# Atmega8_VAW_screen_easyEDA_source.net
KiCad netlist of a schematic drawn in EasyEDA
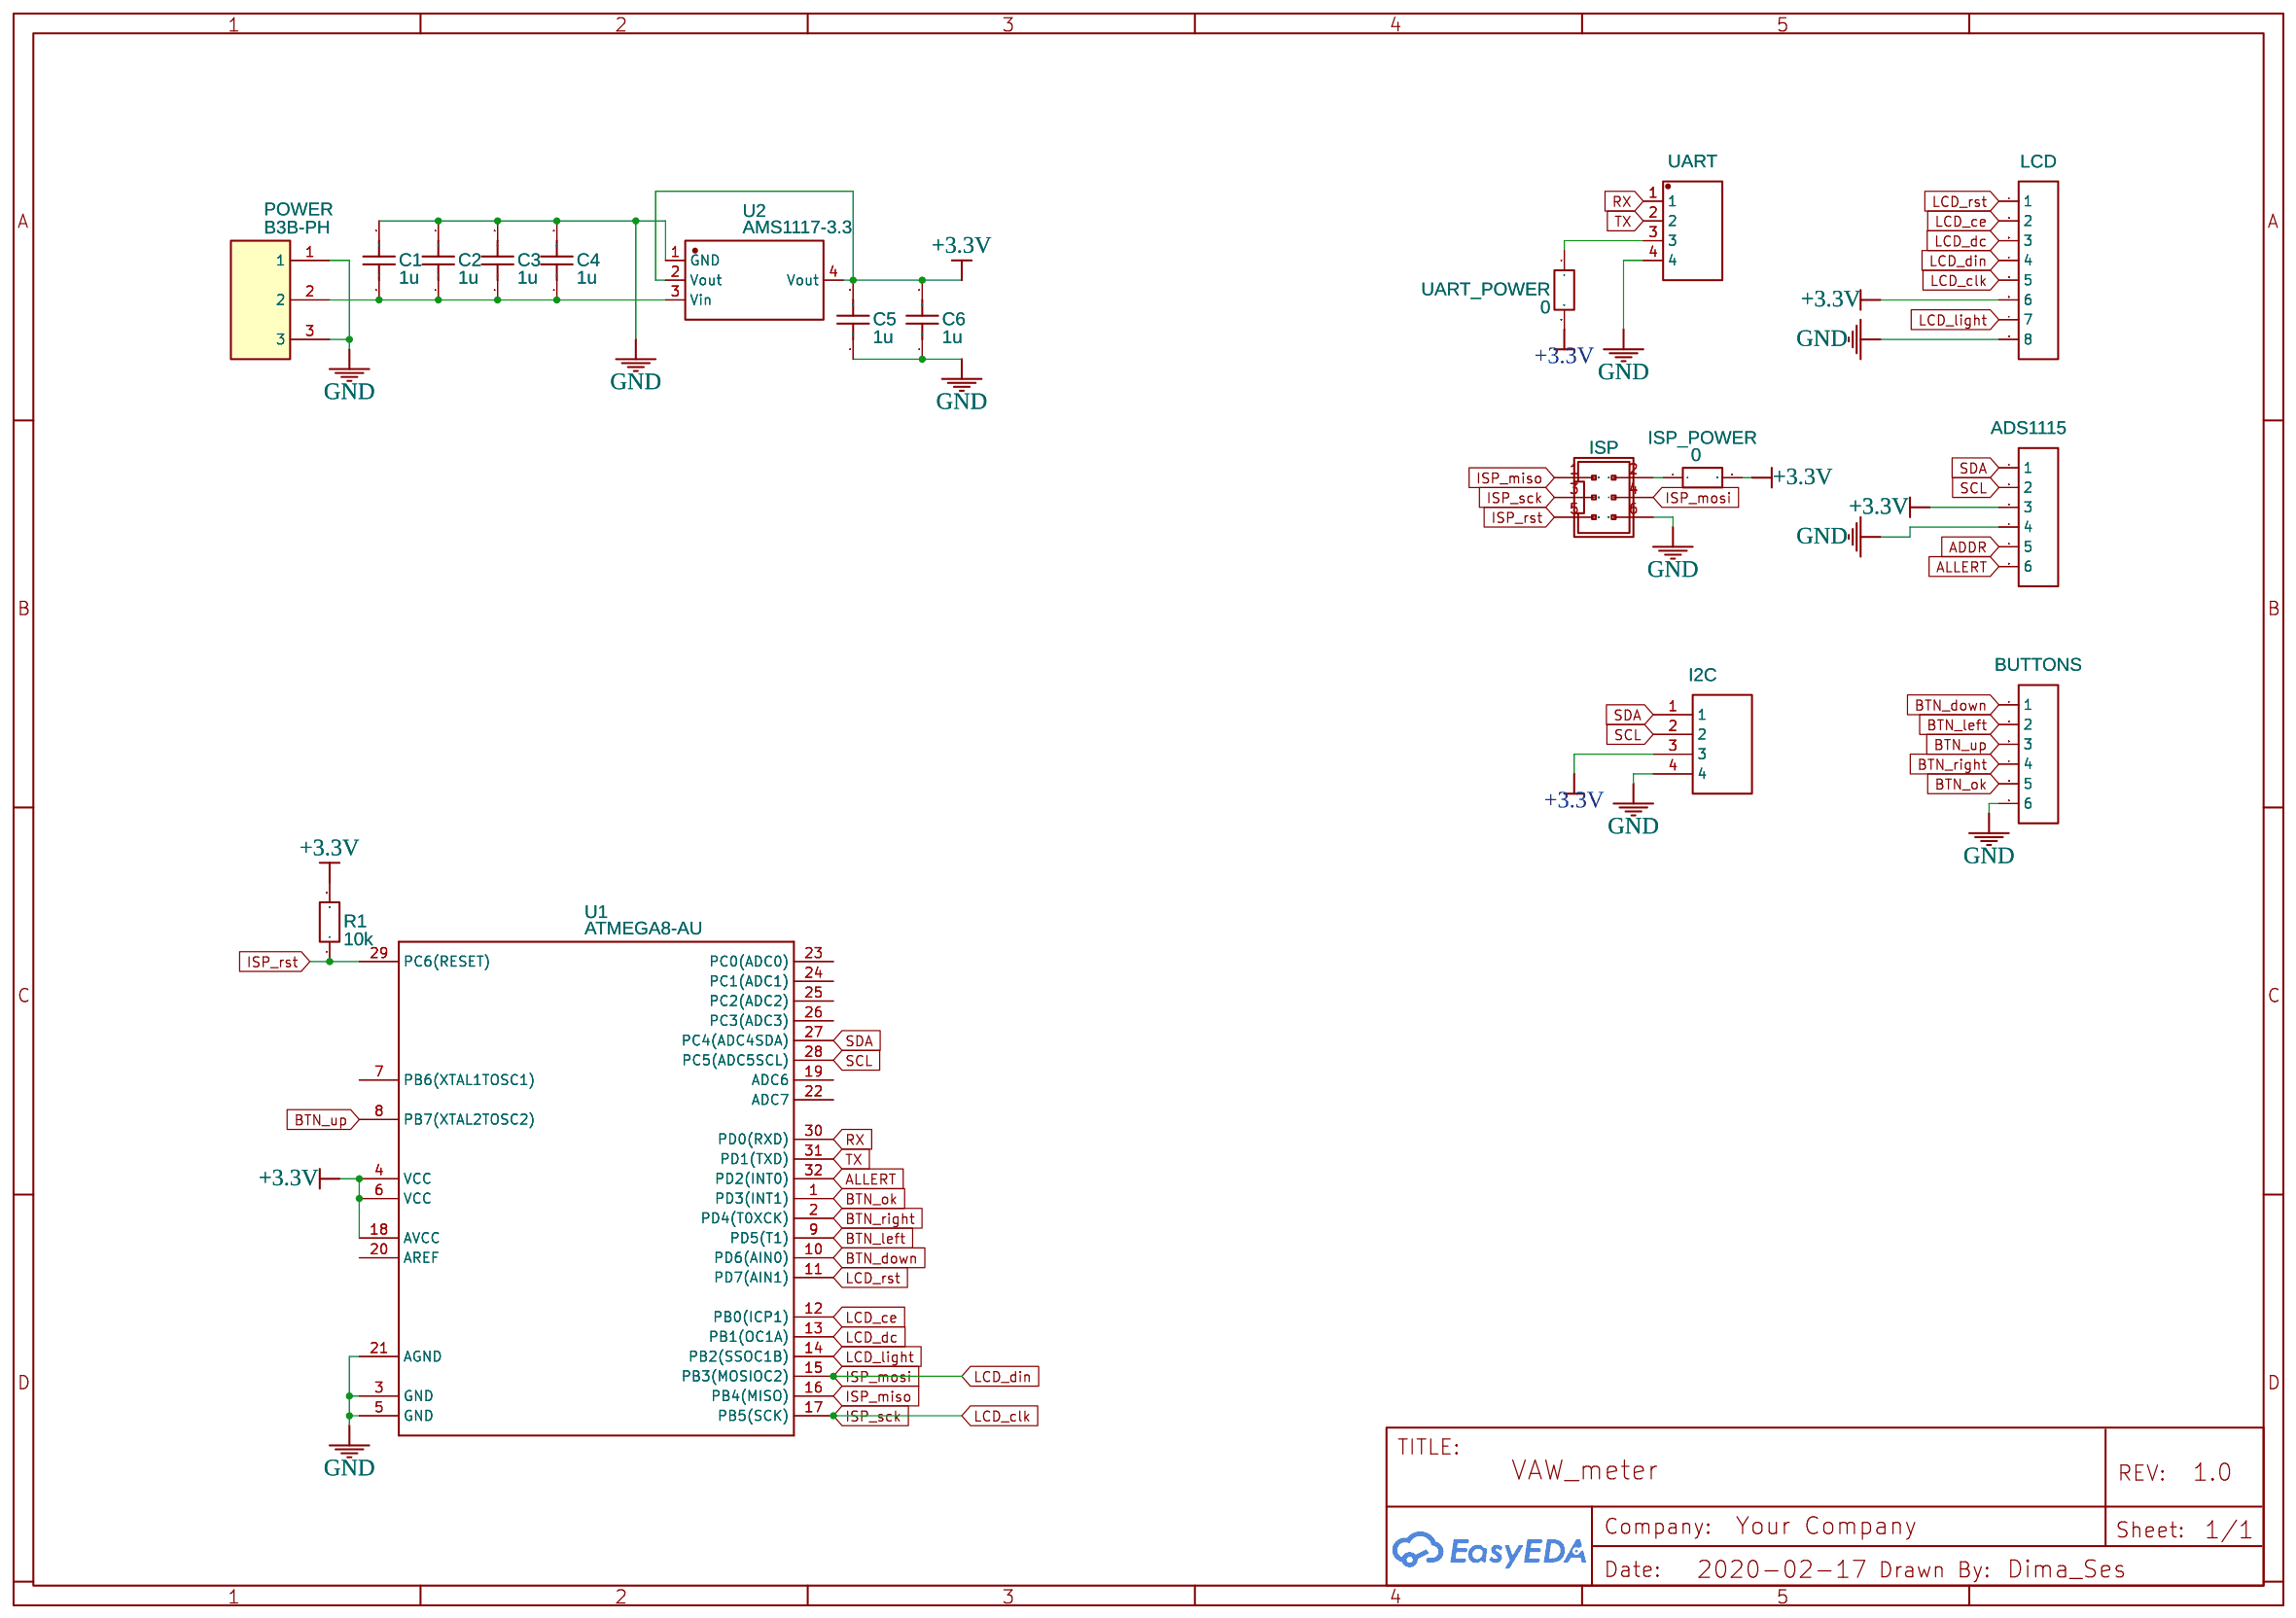
[diagram p0: schematic sheet]

(export (version "E")
  (design (tool "Eeschema 10.0.6"))
  (components
    (comp (ref "ADS1115")
      (value "ADS1115")
      (fields
        (field (name "BOM_Manufacturer Part") "Header-Male-2.54_1x6")
        (field (name "BOM_Supplier Part") "C37208")
      )
      (libsource (lib "") (part "Header-Male-2.54_1x6_1"))
    )
    (comp (ref "BUTTONS")
      (value "Header-Male-2.54_1x6")
      (fields (field (name "BOM_Supplier Part") "C37208"))
      (libsource (lib "") (part "Header-Male-2.54_1x6"))
    )
    (comp (ref "C1") (value "1u") (libsource (lib "") (part "Cap_1206_US")))
    (comp (ref "C2") (value "1u") (libsource (lib "") (part "Cap_1206_US")))
    (comp (ref "C3") (value "1u") (libsource (lib "") (part "Cap_1206_US")))
    (comp (ref "C4") (value "1u") (libsource (lib "") (part "Cap_1206_US")))
    (comp (ref "C5") (value "1u") (libsource (lib "") (part "Cap_1206_US")))
    (comp (ref "C6") (value "1u") (libsource (lib "") (part "Cap_1206_US")))
    (comp (ref "I2C")
      (value "220S-1*4P H=8.5MM Ytype Gold-plated")
      (fields (field (name "BOM_Supplier Part") "C124413"))
      (libsource (lib "") (part "220S-1*4P H=8.5MM Ytype Gold-plated"))
    )
    (comp (ref "ISP")
      (value "BH-06")
      (fields (field (name "BOM_Supplier Part") "BH-14R"))
      (libsource (lib "") (part "BH-06"))
    )
    (comp (ref "ISP_POWER") (value "0") (libsource (lib "") (part "Res_0805(1/8W)_EU_1")))
    (comp (ref "LCD")
      (value "Header-Female-2.54_1x8")
      (fields
        (field (name "BOM_Manufacturer Part") "Female headerHDR1X8-2.54")
        (field (name "BOM_Supplier Part") "C27438")
      )
      (libsource (lib "") (part "Header-Female-2.54_1x8"))
    )
    (comp (ref "POWER")
      (value "B3B-PH")
      (fields
        (field (name "BOM_Manufacturer Part") "B3B-PH-K-S(LF)(SN)")
        (field (name "BOM_Supplier Part") "C131339")
      )
      (libsource (lib "") (part "B3B-PH-K-S(LF)(SN)"))
    )
    (comp (ref "R1") (value "10k") (libsource (lib "") (part "Res_0805(1/8W)_EU_2")))
    (comp (ref "U1") (value "ATMEGA8-AU") (libsource (lib "") (part "ATMEGA8-AU")))
    (comp (ref "U2")
      (value "AMS1117-3.3")
      (fields (field (name "BOM_Supplier Part") "C6186"))
      (libsource (lib "") (part "AMS1117-3.3"))
    )
    (comp (ref "UART")
      (value "UART")
      (fields
        (field (name "BOM_Manufacturer Part") "210S-1*4P L=11.6MMGold-plated black")
        (field (name "BOM_Supplier Part") "C124378")
      )
      (libsource (lib "") (part "Header-Male-2.54_1x4"))
    )
    (comp (ref "UART_POWER") (value "0") (libsource (lib "") (part "Res_0805(1/8W)_EU")))
  )
  (nets
    (net (code "1") (name "+3.3V") (class "Default")
      (node (ref "ADS1115") (pin "3") (pinfunction "3_3") (pintype "input"))
      (node (ref "C5") (pin "2") (pinfunction "2_2") (pintype "unspecified"))
      (node (ref "C6") (pin "2") (pinfunction "2_2") (pintype "unspecified"))
      (node (ref "I2C") (pin "3") (pinfunction "3_3") (pintype "unspecified"))
      (node (ref "ISP_POWER") (pin "2") (pinfunction "2_2") (pintype "unspecified"))
      (node (ref "LCD") (pin "6") (pinfunction "6_6") (pintype "input"))
      (node (ref "R1") (pin "2") (pinfunction "2_2") (pintype "unspecified"))
      (node (ref "U1") (pin "18") (pinfunction "AVCC_18") (pintype "unspecified"))
      (node (ref "U1") (pin "4") (pinfunction "VCC_4") (pintype "passive"))
      (node (ref "U1") (pin "6") (pinfunction "VCC_6") (pintype "passive"))
      (node (ref "U2") (pin "2") (pinfunction "Vout_2") (pintype "unspecified"))
      (node (ref "U2") (pin "4") (pinfunction "Vout_4") (pintype "unspecified"))
      (node (ref "UART_POWER") (pin "2") (pinfunction "2_2") (pintype "unspecified"))
    )
    (net (code "2") (name "ADDR") (class "Default")
      (node (ref "ADS1115") (pin "5") (pinfunction "5_5") (pintype "input"))
    )
    (net (code "3") (name "ALLERT") (class "Default")
      (node (ref "ADS1115") (pin "6") (pinfunction "6_6") (pintype "input"))
      (node (ref "U1") (pin "32") (pinfunction "PD2(INT0)_32") (pintype "unspecified"))
    )
    (net (code "4") (name "BTN_down") (class "Default")
      (node (ref "BUTTONS") (pin "1") (pinfunction "1_1") (pintype "input"))
      (node (ref "U1") (pin "10") (pinfunction "PD6(AIN0)_10") (pintype "unspecified"))
    )
    (net (code "5") (name "BTN_left") (class "Default")
      (node (ref "BUTTONS") (pin "2") (pinfunction "2_2") (pintype "input"))
      (node (ref "U1") (pin "9") (pinfunction "PD5(T1)_9") (pintype "unspecified"))
    )
    (net (code "6") (name "BTN_ok") (class "Default")
      (node (ref "BUTTONS") (pin "5") (pinfunction "5_5") (pintype "input"))
      (node (ref "U1") (pin "1") (pinfunction "PD3(INT1)_1") (pintype "unspecified"))
    )
    (net (code "7") (name "BTN_right") (class "Default")
      (node (ref "BUTTONS") (pin "4") (pinfunction "4_4") (pintype "input"))
      (node (ref "U1") (pin "2") (pinfunction "PD4(T0XCK)_2") (pintype "unspecified"))
    )
    (net (code "8") (name "BTN_up") (class "Default")
      (node (ref "BUTTONS") (pin "3") (pinfunction "3_3") (pintype "input"))
      (node (ref "U1") (pin "8") (pinfunction "PB7(XTAL2TOSC2)_8") (pintype "unspecified"))
    )
    (net (code "9") (name "GND") (class "Default")
      (node (ref "ADS1115") (pin "4") (pinfunction "4_4") (pintype "input"))
      (node (ref "BUTTONS") (pin "6") (pinfunction "6_6") (pintype "input"))
      (node (ref "C1") (pin "2") (pinfunction "2_2") (pintype "unspecified"))
      (node (ref "C2") (pin "2") (pinfunction "2_2") (pintype "unspecified"))
      (node (ref "C3") (pin "2") (pinfunction "2_2") (pintype "unspecified"))
      (node (ref "C4") (pin "2") (pinfunction "2_2") (pintype "unspecified"))
      (node (ref "C5") (pin "1") (pinfunction "1_1") (pintype "unspecified"))
      (node (ref "C6") (pin "1") (pinfunction "1_1") (pintype "unspecified"))
      (node (ref "I2C") (pin "4") (pinfunction "4_4") (pintype "unspecified"))
      (node (ref "ISP") (pin "6") (pinfunction "6_6") (pintype "unspecified"))
      (node (ref "LCD") (pin "8") (pinfunction "8_8") (pintype "input"))
      (node (ref "POWER") (pin "1") (pinfunction "1_1") (pintype "input"))
      (node (ref "POWER") (pin "3") (pinfunction "3_3") (pintype "input"))
      (node (ref "U1") (pin "21") (pinfunction "AGND_21") (pintype "passive"))
      (node (ref "U1") (pin "3") (pinfunction "GND_3") (pintype "passive"))
      (node (ref "U1") (pin "5") (pinfunction "GND_5") (pintype "passive"))
      (node (ref "U2") (pin "1") (pinfunction "GND_1") (pintype "unspecified"))
      (node (ref "UART") (pin "4") (pinfunction "4_4") (pintype "unspecified"))
    )
    (net (code "10") (name "ISP_miso") (class "Default")
      (node (ref "ISP") (pin "1") (pinfunction "1_1") (pintype "unspecified"))
      (node (ref "U1") (pin "16") (pinfunction "PB4(MISO)_16") (pintype "unspecified"))
    )
    (net (code "11") (name "ISP_mosi") (class "Default")
      (node (ref "ISP") (pin "4") (pinfunction "4_4") (pintype "unspecified"))
      (node (ref "LCD") (pin "4") (pinfunction "4_4") (pintype "input"))
      (node (ref "U1") (pin "15") (pinfunction "PB3(MOSIOC2)_15") (pintype "unspecified"))
    )
    (net (code "12") (name "ISP_rst") (class "Default")
      (node (ref "ISP") (pin "5") (pinfunction "5_5") (pintype "unspecified"))
      (node (ref "R1") (pin "1") (pinfunction "1_1") (pintype "unspecified"))
      (node (ref "U1") (pin "29") (pinfunction "PC6(RESET)_29") (pintype "unspecified"))
    )
    (net (code "13") (name "ISP_sck") (class "Default")
      (node (ref "ISP") (pin "3") (pinfunction "3_3") (pintype "unspecified"))
      (node (ref "LCD") (pin "5") (pinfunction "5_5") (pintype "input"))
      (node (ref "U1") (pin "17") (pinfunction "PB5(SCK)_17") (pintype "unspecified"))
    )
    (net (code "14") (name "LCD_ce") (class "Default")
      (node (ref "LCD") (pin "2") (pinfunction "2_2") (pintype "input"))
      (node (ref "U1") (pin "12") (pinfunction "PB0(ICP1)_12") (pintype "unspecified"))
    )
    (net (code "15") (name "LCD_dc") (class "Default")
      (node (ref "LCD") (pin "3") (pinfunction "3_3") (pintype "input"))
      (node (ref "U1") (pin "13") (pinfunction "PB1(OC1A)_13") (pintype "unspecified"))
    )
    (net (code "16") (name "LCD_light") (class "Default")
      (node (ref "LCD") (pin "7") (pinfunction "7_7") (pintype "input"))
      (node (ref "U1") (pin "14") (pinfunction "PB2(SSOC1B)_14") (pintype "unspecified"))
    )
    (net (code "17") (name "LCD_rst") (class "Default")
      (node (ref "LCD") (pin "1") (pinfunction "1_1") (pintype "input"))
      (node (ref "U1") (pin "11") (pinfunction "PD7(AIN1)_11") (pintype "unspecified"))
    )
    (net (code "18") (name "Net-(ISP-Pad2)") (class "Default")
      (node (ref "ISP") (pin "2") (pinfunction "2_2") (pintype "unspecified"))
      (node (ref "ISP_POWER") (pin "1") (pinfunction "1_1") (pintype "unspecified"))
    )
    (net (code "19") (name "Net-(U2-Vin)") (class "Default")
      (node (ref "C1") (pin "1") (pinfunction "1_1") (pintype "unspecified"))
      (node (ref "C2") (pin "1") (pinfunction "1_1") (pintype "unspecified"))
      (node (ref "C3") (pin "1") (pinfunction "1_1") (pintype "unspecified"))
      (node (ref "C4") (pin "1") (pinfunction "1_1") (pintype "unspecified"))
      (node (ref "POWER") (pin "2") (pinfunction "2_2") (pintype "input"))
      (node (ref "U2") (pin "3") (pinfunction "Vin_3") (pintype "unspecified"))
    )
    (net (code "20") (name "Net-(UART-Pad3)") (class "Default")
      (node (ref "UART") (pin "3") (pinfunction "3_3") (pintype "unspecified"))
      (node (ref "UART_POWER") (pin "1") (pinfunction "1_1") (pintype "unspecified"))
    )
    (net (code "21") (name "RX") (class "Default")
      (node (ref "U1") (pin "30") (pinfunction "PD0(RXD)_30") (pintype "unspecified"))
      (node (ref "UART") (pin "1") (pinfunction "1_1") (pintype "unspecified"))
    )
    (net (code "22") (name "SCL") (class "Default")
      (node (ref "ADS1115") (pin "2") (pinfunction "2_2") (pintype "input"))
      (node (ref "I2C") (pin "2") (pinfunction "2_2") (pintype "unspecified"))
      (node (ref "U1") (pin "28") (pinfunction "PC5(ADC5SCL)_28") (pintype "unspecified"))
    )
    (net (code "23") (name "SDA") (class "Default")
      (node (ref "ADS1115") (pin "1") (pinfunction "1_1") (pintype "input"))
      (node (ref "I2C") (pin "1") (pinfunction "1_1") (pintype "unspecified"))
      (node (ref "U1") (pin "27") (pinfunction "PC4(ADC4SDA)_27") (pintype "unspecified"))
    )
    (net (code "24") (name "TX") (class "Default")
      (node (ref "U1") (pin "31") (pinfunction "PD1(TXD)_31") (pintype "unspecified"))
      (node (ref "UART") (pin "2") (pinfunction "2_2") (pintype "unspecified"))
    )
    (net (code "25") (name "unconnected-(U1-ADC6-Pad19)") (class "Default")
      (node (ref "U1") (pin "19") (pinfunction "ADC6_19") (pintype "unspecified"))
    )
    (net (code "26") (name "unconnected-(U1-ADC7-Pad22)") (class "Default")
      (node (ref "U1") (pin "22") (pinfunction "ADC7_22") (pintype "unspecified"))
    )
    (net (code "27") (name "unconnected-(U1-AREF-Pad20)") (class "Default")
      (node (ref "U1") (pin "20") (pinfunction "AREF_20") (pintype "unspecified"))
    )
    (net (code "28") (name "unconnected-(U1-PB6(XTAL1TOSC1)-Pad7)") (class "Default")
      (node (ref "U1") (pin "7") (pinfunction "PB6(XTAL1TOSC1)_7") (pintype "unspecified"))
    )
    (net (code "29") (name "unconnected-(U1-PC0(ADC0)-Pad23)") (class "Default")
      (node (ref "U1") (pin "23") (pinfunction "PC0(ADC0)_23") (pintype "unspecified"))
    )
    (net (code "30") (name "unconnected-(U1-PC1(ADC1)-Pad24)") (class "Default")
      (node (ref "U1") (pin "24") (pinfunction "PC1(ADC1)_24") (pintype "unspecified"))
    )
    (net (code "31") (name "unconnected-(U1-PC2(ADC2)-Pad25)") (class "Default")
      (node (ref "U1") (pin "25") (pinfunction "PC2(ADC2)_25") (pintype "unspecified"))
    )
    (net (code "32") (name "unconnected-(U1-PC3(ADC3)-Pad26)") (class "Default")
      (node (ref "U1") (pin "26") (pinfunction "PC3(ADC3)_26") (pintype "unspecified"))
    )
  )
)
